# icE1usb-proto.net
KiCad netlist of a schematic drawn in EAGLE
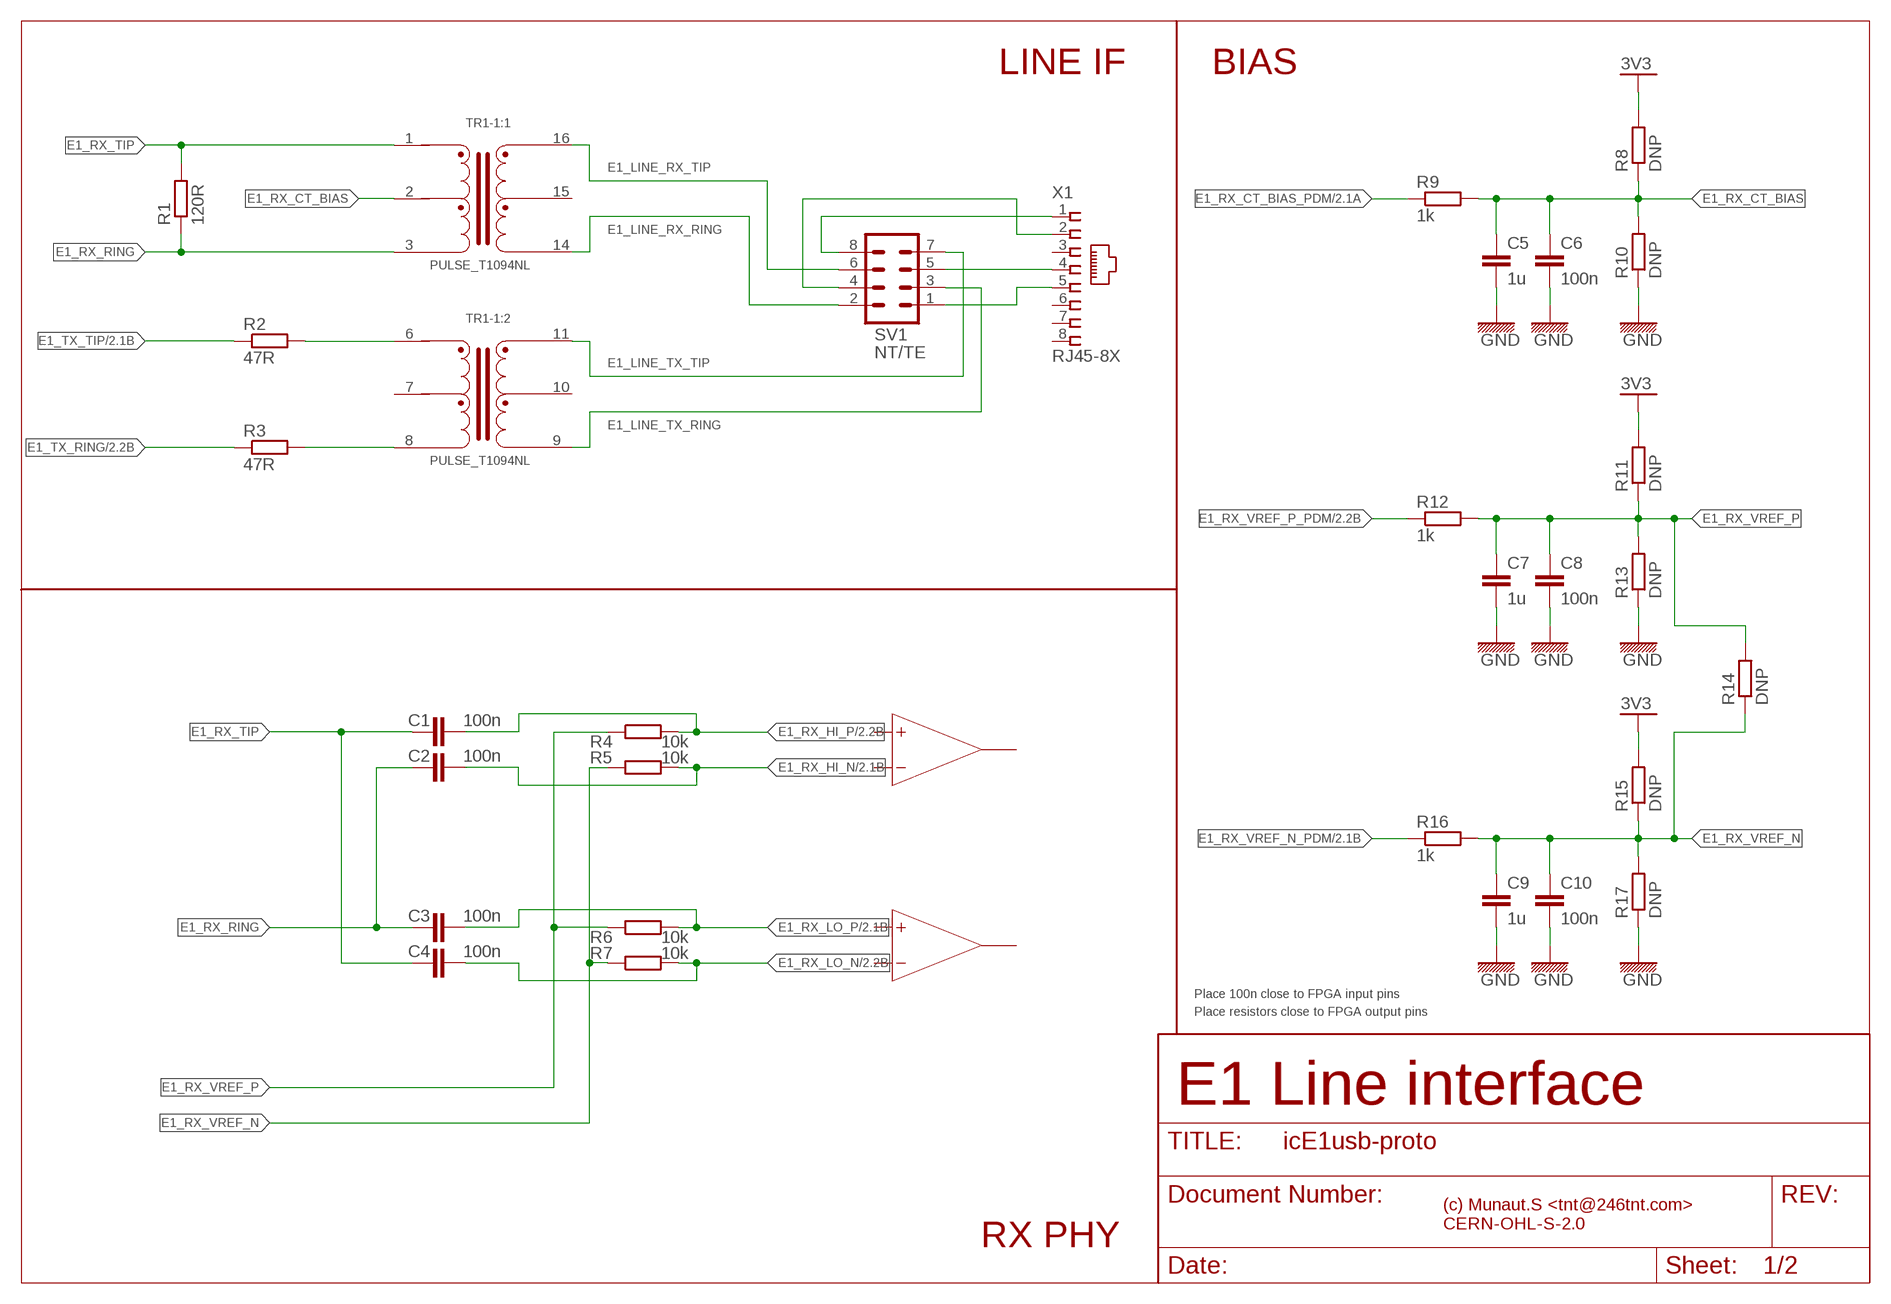
[diagram p0: schematic, sheet 1]
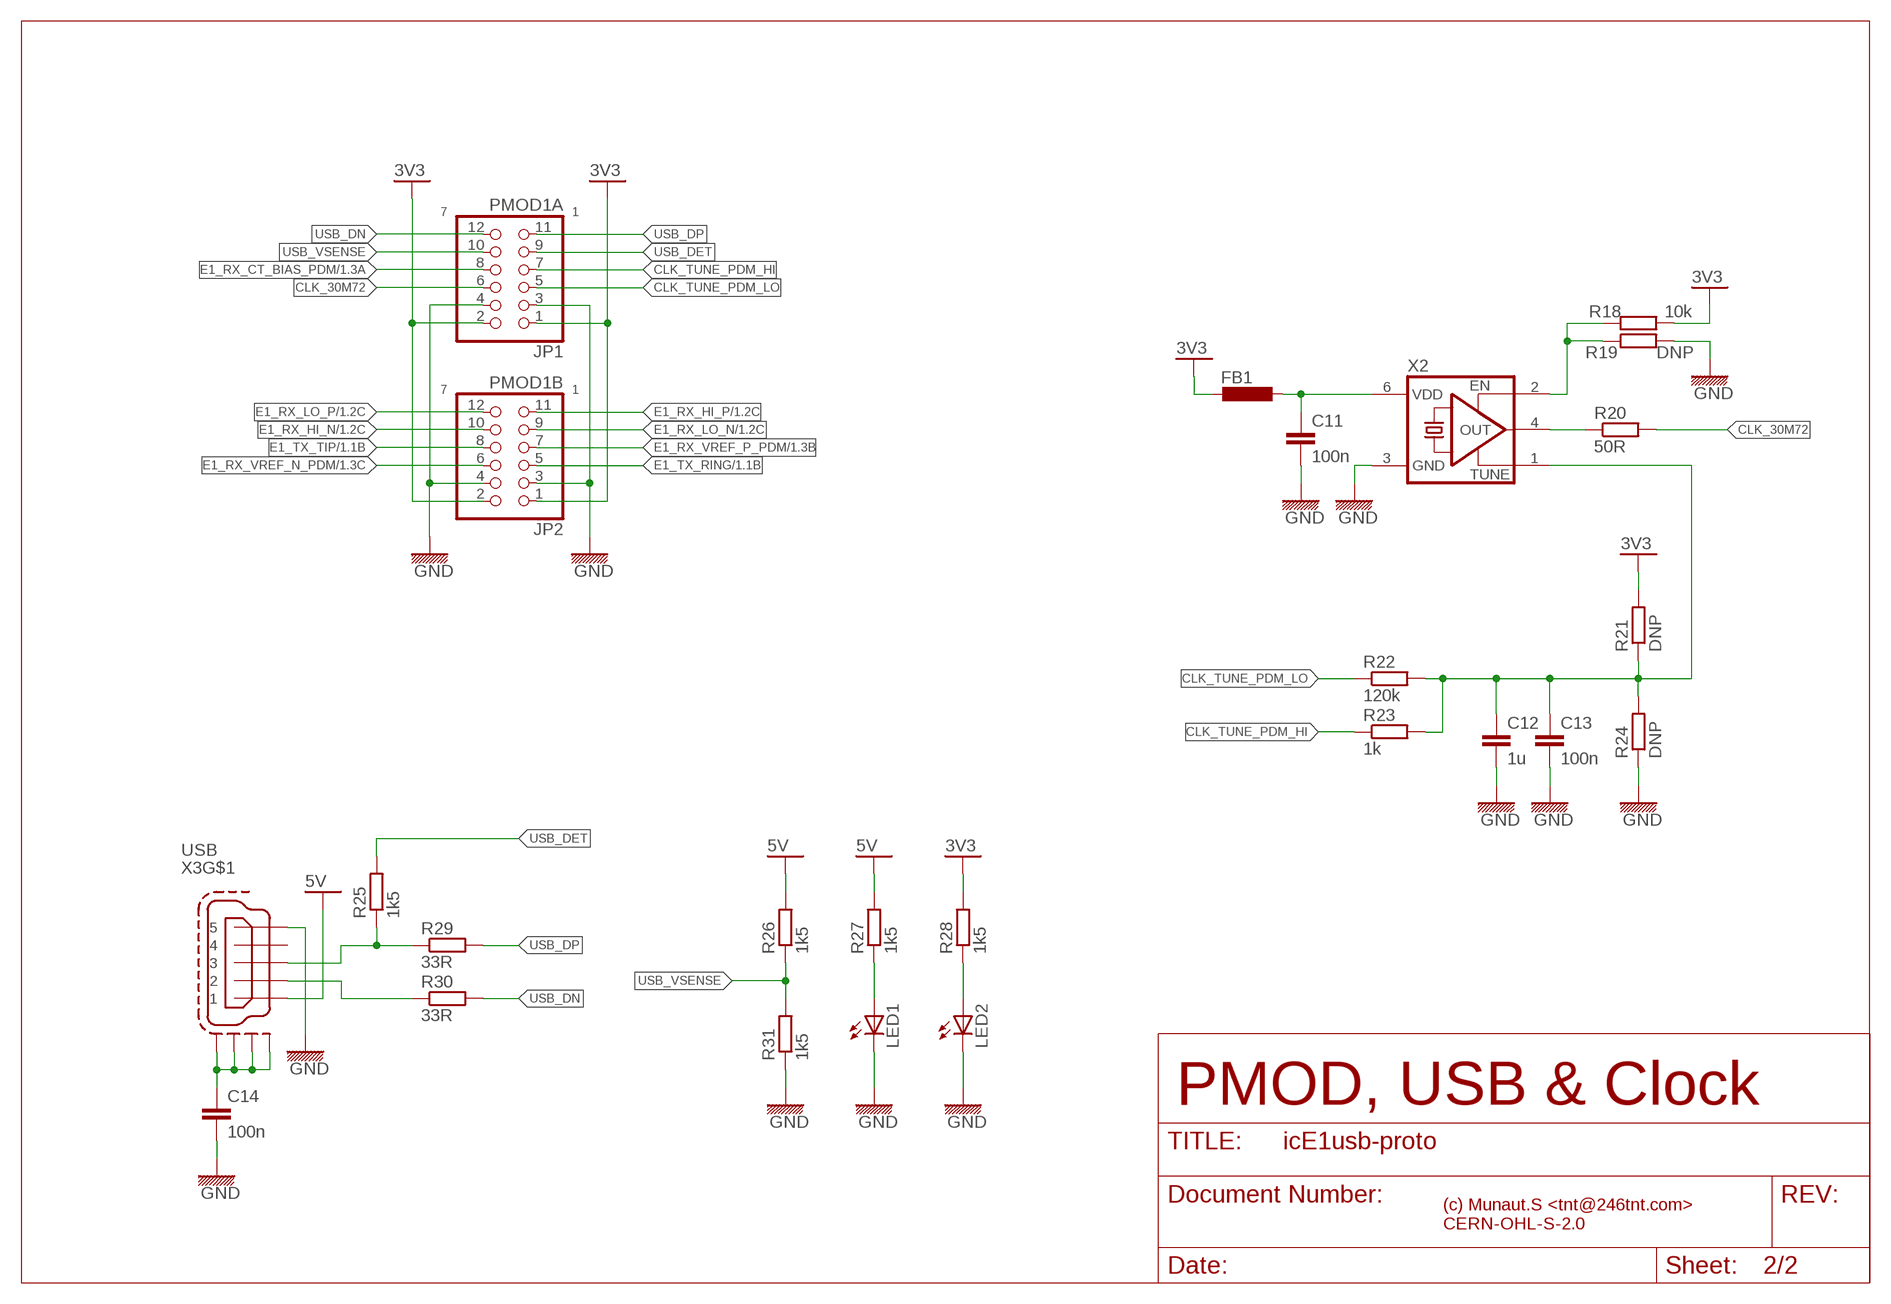
[diagram p1: schematic, sheet 2]

(export (version "E")
  (design (tool "Eeschema 10.0.6"))
  (components
    (comp (ref "C1")
      (value "100n")
      (footprint "eagle-import:0603")
      (libsource (lib "eagle-import") (part "C-EU_0603"))
    )
    (comp (ref "C2")
      (value "100n")
      (footprint "eagle-import:0603")
      (libsource (lib "eagle-import") (part "C-EU_0603"))
    )
    (comp (ref "C3")
      (value "100n")
      (footprint "eagle-import:0603")
      (libsource (lib "eagle-import") (part "C-EU_0603"))
    )
    (comp (ref "C4")
      (value "100n")
      (footprint "eagle-import:0603")
      (libsource (lib "eagle-import") (part "C-EU_0603"))
    )
    (comp (ref "C5")
      (value "1u")
      (footprint "eagle-import:0603")
      (libsource (lib "eagle-import") (part "C-EU_0603"))
    )
    (comp (ref "C6")
      (value "100n")
      (footprint "eagle-import:0603")
      (libsource (lib "eagle-import") (part "C-EU_0603"))
    )
    (comp (ref "C7")
      (value "1u")
      (footprint "eagle-import:0603")
      (libsource (lib "eagle-import") (part "C-EU_0603"))
    )
    (comp (ref "C8")
      (value "100n")
      (footprint "eagle-import:0603")
      (libsource (lib "eagle-import") (part "C-EU_0603"))
    )
    (comp (ref "C9")
      (value "1u")
      (footprint "eagle-import:0603")
      (libsource (lib "eagle-import") (part "C-EU_0603"))
    )
    (comp (ref "C10")
      (value "100n")
      (footprint "eagle-import:0603")
      (libsource (lib "eagle-import") (part "C-EU_0603"))
    )
    (comp (ref "R1")
      (value "120R")
      (footprint "eagle-import:0603_A")
      (libsource (lib "eagle-import") (part "R-EU_0603_A"))
    )
    (comp (ref "R2")
      (value "47R")
      (footprint "eagle-import:0603_A")
      (libsource (lib "eagle-import") (part "R-EU_0603_A"))
    )
    (comp (ref "R3")
      (value "47R")
      (footprint "eagle-import:0603_A")
      (libsource (lib "eagle-import") (part "R-EU_0603_A"))
    )
    (comp (ref "R4")
      (value "10k")
      (footprint "eagle-import:0603_A")
      (libsource (lib "eagle-import") (part "R-EU_0603_A"))
    )
    (comp (ref "R5")
      (value "10k")
      (footprint "eagle-import:0603_A")
      (libsource (lib "eagle-import") (part "R-EU_0603_A"))
    )
    (comp (ref "R6")
      (value "10k")
      (footprint "eagle-import:0603_A")
      (libsource (lib "eagle-import") (part "R-EU_0603_A"))
    )
    (comp (ref "R7")
      (value "10k")
      (footprint "eagle-import:0603_A")
      (libsource (lib "eagle-import") (part "R-EU_0603_A"))
    )
    (comp (ref "R8")
      (value "DNP")
      (footprint "eagle-import:0603_A")
      (libsource (lib "eagle-import") (part "R-EU_0603_A"))
    )
    (comp (ref "R9")
      (value "1k")
      (footprint "eagle-import:0603_A")
      (libsource (lib "eagle-import") (part "R-EU_0603_A"))
    )
    (comp (ref "R10")
      (value "DNP")
      (footprint "eagle-import:0603_A")
      (libsource (lib "eagle-import") (part "R-EU_0603_A"))
    )
    (comp (ref "R11")
      (value "DNP")
      (footprint "eagle-import:0603_A")
      (libsource (lib "eagle-import") (part "R-EU_0603_A"))
    )
    (comp (ref "R12")
      (value "1k")
      (footprint "eagle-import:0603_A")
      (libsource (lib "eagle-import") (part "R-EU_0603_A"))
    )
    (comp (ref "R13")
      (value "DNP")
      (footprint "eagle-import:0603_A")
      (libsource (lib "eagle-import") (part "R-EU_0603_A"))
    )
    (comp (ref "R14")
      (value "DNP")
      (footprint "eagle-import:0603_A")
      (libsource (lib "eagle-import") (part "R-EU_0603_A"))
    )
    (comp (ref "R15")
      (value "DNP")
      (footprint "eagle-import:0603_A")
      (libsource (lib "eagle-import") (part "R-EU_0603_A"))
    )
    (comp (ref "R16")
      (value "1k")
      (footprint "eagle-import:0603_A")
      (libsource (lib "eagle-import") (part "R-EU_0603_A"))
    )
    (comp (ref "R17")
      (value "DNP")
      (footprint "eagle-import:0603_A")
      (libsource (lib "eagle-import") (part "R-EU_0603_A"))
    )
    (comp (ref "SV1")
      (value "NT/TE")
      (footprint "eagle-import:MA04-2")
      (libsource (lib "eagle-import") (part "MA04-2"))
    )
    (comp (ref "TR1")
      (value "PULSE_T1094NL")
      (footprint "eagle-import:PULSE_BH")
      (libsource (lib "eagle-import") (part "PULSE_T1094NL"))
    )
    (comp (ref "X1")
      (value "RJ45-8X")
      (footprint "eagle-import:RJ45-NO-SHIELD")
      (libsource (lib "eagle-import") (part "RJ45-8X"))
    )
    (comp (ref "C11")
      (value "100n")
      (footprint "eagle-import:0603")
      (libsource (lib "eagle-import") (part "C-EU_0603"))
    )
    (comp (ref "C12")
      (value "1u")
      (footprint "eagle-import:0603")
      (libsource (lib "eagle-import") (part "C-EU_0603"))
    )
    (comp (ref "C13")
      (value "100n")
      (footprint "eagle-import:0603")
      (libsource (lib "eagle-import") (part "C-EU_0603"))
    )
    (comp (ref "C14")
      (value "100n")
      (footprint "eagle-import:0603")
      (libsource (lib "eagle-import") (part "C-EU_0603"))
    )
    (comp (ref "FB1")
      (value "FBEAD_0603")
      (footprint "eagle-import:0603")
      (libsource (lib "eagle-import") (part "FBEAD_0603"))
    )
    (comp (ref "JP1")
      (value "PMOD1A")
      (footprint "eagle-import:2X06_90")
      (libsource (lib "eagle-import") (part "PINHD-2X6/90"))
    )
    (comp (ref "JP2")
      (value "PMOD1B")
      (footprint "eagle-import:2X06_90")
      (libsource (lib "eagle-import") (part "PINHD-2X6/90"))
    )
    (comp (ref "LED1")
      (value "LEDCHIPLED_0603")
      (footprint "eagle-import:CHIPLED_0603")
      (libsource (lib "eagle-import") (part "LEDCHIPLED_0603"))
    )
    (comp (ref "LED2")
      (value "LEDCHIPLED_0603")
      (footprint "eagle-import:CHIPLED_0603")
      (libsource (lib "eagle-import") (part "LEDCHIPLED_0603"))
    )
    (comp (ref "R18")
      (value "10k")
      (footprint "eagle-import:0603_A")
      (libsource (lib "eagle-import") (part "R-EU_0603_A"))
    )
    (comp (ref "R19")
      (value "DNP")
      (footprint "eagle-import:0603_A")
      (libsource (lib "eagle-import") (part "R-EU_0603_A"))
    )
    (comp (ref "R20")
      (value "50R")
      (footprint "eagle-import:0603_A")
      (libsource (lib "eagle-import") (part "R-EU_0603_A"))
    )
    (comp (ref "R21")
      (value "DNP")
      (footprint "eagle-import:0603_A")
      (libsource (lib "eagle-import") (part "R-EU_0603_A"))
    )
    (comp (ref "R22")
      (value "120k")
      (footprint "eagle-import:0603_A")
      (libsource (lib "eagle-import") (part "R-EU_0603_A"))
    )
    (comp (ref "R23")
      (value "1k")
      (footprint "eagle-import:0603_A")
      (libsource (lib "eagle-import") (part "R-EU_0603_A"))
    )
    (comp (ref "R24")
      (value "DNP")
      (footprint "eagle-import:0603_A")
      (libsource (lib "eagle-import") (part "R-EU_0603_A"))
    )
    (comp (ref "R25")
      (value "1k5")
      (footprint "eagle-import:0603_A")
      (libsource (lib "eagle-import") (part "R-EU_0603_A"))
    )
    (comp (ref "R26")
      (value "1k5")
      (footprint "eagle-import:0603_A")
      (libsource (lib "eagle-import") (part "R-EU_0603_A"))
    )
    (comp (ref "R27")
      (value "1k5")
      (footprint "eagle-import:0603_A")
      (libsource (lib "eagle-import") (part "R-EU_0603_A"))
    )
    (comp (ref "R28")
      (value "1k5")
      (footprint "eagle-import:0603_A")
      (libsource (lib "eagle-import") (part "R-EU_0603_A"))
    )
    (comp (ref "R29")
      (value "33R")
      (footprint "eagle-import:0603_A")
      (libsource (lib "eagle-import") (part "R-EU_0603_A"))
    )
    (comp (ref "R30")
      (value "33R")
      (footprint "eagle-import:0603_A")
      (libsource (lib "eagle-import") (part "R-EU_0603_A"))
    )
    (comp (ref "R31")
      (value "1k5")
      (footprint "eagle-import:0603_A")
      (libsource (lib "eagle-import") (part "R-EU_0603_A"))
    )
    (comp (ref "X2")
      (value "XTAL_OSC_ET_CFPV-45/46")
      (footprint "eagle-import:CFPV-45_46")
      (libsource (lib "eagle-import") (part "XTAL_OSC_ET_CFPV-45/46"))
    )
    (comp (ref "X3")
      (value "USB")
      (footprint "eagle-import:32005-201")
      (libsource (lib "eagle-import") (part "MINI-USB-SCHIELD-32005-201"))
    )
  )
  (nets
    (net (code "1") (name "3V3") (class "Default")
      (node (ref "FB1") (pin "1") (pinfunction "1_1") (pintype "passive"))
      (node (ref "JP1") (pin "1") (pinfunction "1_1") (pintype "passive"))
      (node (ref "JP1") (pin "2") (pinfunction "2_2") (pintype "passive"))
      (node (ref "JP2") (pin "1") (pinfunction "1_1") (pintype "passive"))
      (node (ref "JP2") (pin "2") (pinfunction "2_2") (pintype "passive"))
      (node (ref "R11") (pin "2") (pinfunction "2_2") (pintype "passive"))
      (node (ref "R15") (pin "2") (pinfunction "2_2") (pintype "passive"))
      (node (ref "R18") (pin "2") (pinfunction "2_2") (pintype "passive"))
      (node (ref "R21") (pin "2") (pinfunction "2_2") (pintype "passive"))
      (node (ref "R28") (pin "2") (pinfunction "2_2") (pintype "passive"))
      (node (ref "R8") (pin "2") (pinfunction "2_2") (pintype "passive"))
    )
    (net (code "2") (name "5V") (class "Default")
      (node (ref "R26") (pin "2") (pinfunction "2_2") (pintype "passive"))
      (node (ref "R27") (pin "2") (pinfunction "2_2") (pintype "passive"))
      (node (ref "X3") (pin "1") (pinfunction "1_1") (pintype "passive"))
    )
    (net (code "3") (name "CLK_30M72") (class "Default")
      (node (ref "JP1") (pin "6") (pinfunction "6_6") (pintype "passive"))
      (node (ref "R20") (pin "2") (pinfunction "2_2") (pintype "passive"))
    )
    (net (code "4") (name "CLK_TUNE_PDM_HI") (class "Default")
      (node (ref "JP1") (pin "7") (pinfunction "7_7") (pintype "passive"))
      (node (ref "R23") (pin "1") (pinfunction "1_1") (pintype "passive"))
    )
    (net (code "5") (name "CLK_TUNE_PDM_LO") (class "Default")
      (node (ref "JP1") (pin "5") (pinfunction "5_5") (pintype "passive"))
      (node (ref "R22") (pin "1") (pinfunction "1_1") (pintype "passive"))
    )
    (net (code "6") (name "E1_LINE_RX_RING") (class "Default")
      (node (ref "SV1") (pin "2") (pinfunction "2_2") (pintype "passive"))
      (node (ref "TR1") (pin "14") (pinfunction "P$3_14") (pintype "bidirectional"))
    )
    (net (code "7") (name "E1_LINE_RX_TIP") (class "Default")
      (node (ref "SV1") (pin "6") (pinfunction "6_6") (pintype "passive"))
      (node (ref "TR1") (pin "16") (pinfunction "P$1_16") (pintype "bidirectional"))
    )
    (net (code "8") (name "E1_LINE_TX_RING") (class "Default")
      (node (ref "SV1") (pin "3") (pinfunction "3_3") (pintype "passive"))
      (node (ref "TR1") (pin "9") (pinfunction "P$3_9") (pintype "bidirectional"))
    )
    (net (code "9") (name "E1_LINE_TX_TIP") (class "Default")
      (node (ref "SV1") (pin "7") (pinfunction "7_7") (pintype "passive"))
      (node (ref "TR1") (pin "11") (pinfunction "P$1_11") (pintype "bidirectional"))
    )
    (net (code "10") (name "E1_RX_CT_BIAS") (class "Default")
      (node (ref "C5") (pin "1") (pinfunction "1_1") (pintype "passive"))
      (node (ref "C6") (pin "1") (pinfunction "1_1") (pintype "passive"))
      (node (ref "R10") (pin "2") (pinfunction "2_2") (pintype "passive"))
      (node (ref "R8") (pin "1") (pinfunction "1_1") (pintype "passive"))
      (node (ref "R9") (pin "2") (pinfunction "2_2") (pintype "passive"))
      (node (ref "TR1") (pin "2") (pinfunction "P$5_2") (pintype "bidirectional"))
    )
    (net (code "11") (name "E1_RX_CT_BIAS_PDM") (class "Default")
      (node (ref "JP1") (pin "8") (pinfunction "8_8") (pintype "passive"))
      (node (ref "R9") (pin "1") (pinfunction "1_1") (pintype "passive"))
    )
    (net (code "12") (name "E1_RX_HI_N") (class "Default")
      (node (ref "C2") (pin "2") (pinfunction "2_2") (pintype "passive"))
      (node (ref "JP2") (pin "10") (pinfunction "10_10") (pintype "passive"))
      (node (ref "R5") (pin "2") (pinfunction "2_2") (pintype "passive"))
    )
    (net (code "13") (name "E1_RX_HI_P") (class "Default")
      (node (ref "C1") (pin "2") (pinfunction "2_2") (pintype "passive"))
      (node (ref "JP2") (pin "11") (pinfunction "11_11") (pintype "passive"))
      (node (ref "R4") (pin "2") (pinfunction "2_2") (pintype "passive"))
    )
    (net (code "14") (name "E1_RX_LO_N") (class "Default")
      (node (ref "C4") (pin "2") (pinfunction "2_2") (pintype "passive"))
      (node (ref "JP2") (pin "9") (pinfunction "9_9") (pintype "passive"))
      (node (ref "R7") (pin "2") (pinfunction "2_2") (pintype "passive"))
    )
    (net (code "15") (name "E1_RX_LO_P") (class "Default")
      (node (ref "C3") (pin "2") (pinfunction "2_2") (pintype "passive"))
      (node (ref "JP2") (pin "12") (pinfunction "12_12") (pintype "passive"))
      (node (ref "R6") (pin "2") (pinfunction "2_2") (pintype "passive"))
    )
    (net (code "16") (name "E1_RX_RING") (class "Default")
      (node (ref "C2") (pin "1") (pinfunction "1_1") (pintype "passive"))
      (node (ref "C3") (pin "1") (pinfunction "1_1") (pintype "passive"))
      (node (ref "R1") (pin "1") (pinfunction "1_1") (pintype "passive"))
      (node (ref "TR1") (pin "3") (pinfunction "P$6_3") (pintype "bidirectional"))
    )
    (net (code "17") (name "E1_RX_TIP") (class "Default")
      (node (ref "C1") (pin "1") (pinfunction "1_1") (pintype "passive"))
      (node (ref "C4") (pin "1") (pinfunction "1_1") (pintype "passive"))
      (node (ref "R1") (pin "2") (pinfunction "2_2") (pintype "passive"))
      (node (ref "TR1") (pin "1") (pinfunction "P$4_1") (pintype "bidirectional"))
    )
    (net (code "18") (name "E1_RX_VREF_N") (class "Default")
      (node (ref "C10") (pin "1") (pinfunction "1_1") (pintype "passive"))
      (node (ref "C9") (pin "1") (pinfunction "1_1") (pintype "passive"))
      (node (ref "R14") (pin "1") (pinfunction "1_1") (pintype "passive"))
      (node (ref "R15") (pin "1") (pinfunction "1_1") (pintype "passive"))
      (node (ref "R16") (pin "2") (pinfunction "2_2") (pintype "passive"))
      (node (ref "R17") (pin "2") (pinfunction "2_2") (pintype "passive"))
      (node (ref "R5") (pin "1") (pinfunction "1_1") (pintype "passive"))
      (node (ref "R7") (pin "1") (pinfunction "1_1") (pintype "passive"))
    )
    (net (code "19") (name "E1_RX_VREF_N_PDM") (class "Default")
      (node (ref "JP2") (pin "6") (pinfunction "6_6") (pintype "passive"))
      (node (ref "R16") (pin "1") (pinfunction "1_1") (pintype "passive"))
    )
    (net (code "20") (name "E1_RX_VREF_P") (class "Default")
      (node (ref "C7") (pin "1") (pinfunction "1_1") (pintype "passive"))
      (node (ref "C8") (pin "1") (pinfunction "1_1") (pintype "passive"))
      (node (ref "R11") (pin "1") (pinfunction "1_1") (pintype "passive"))
      (node (ref "R12") (pin "2") (pinfunction "2_2") (pintype "passive"))
      (node (ref "R13") (pin "2") (pinfunction "2_2") (pintype "passive"))
      (node (ref "R14") (pin "2") (pinfunction "2_2") (pintype "passive"))
      (node (ref "R4") (pin "1") (pinfunction "1_1") (pintype "passive"))
      (node (ref "R6") (pin "1") (pinfunction "1_1") (pintype "passive"))
    )
    (net (code "21") (name "E1_RX_VREF_P_PDM") (class "Default")
      (node (ref "JP2") (pin "7") (pinfunction "7_7") (pintype "passive"))
      (node (ref "R12") (pin "1") (pinfunction "1_1") (pintype "passive"))
    )
    (net (code "22") (name "E1_TX_RING") (class "Default")
      (node (ref "JP2") (pin "5") (pinfunction "5_5") (pintype "passive"))
      (node (ref "R3") (pin "1") (pinfunction "1_1") (pintype "passive"))
    )
    (net (code "23") (name "E1_TX_TIP") (class "Default")
      (node (ref "JP2") (pin "8") (pinfunction "8_8") (pintype "passive"))
      (node (ref "R2") (pin "1") (pinfunction "1_1") (pintype "passive"))
    )
    (net (code "24") (name "GND") (class "Default")
      (node (ref "C10") (pin "2") (pinfunction "2_2") (pintype "passive"))
      (node (ref "C11") (pin "2") (pinfunction "2_2") (pintype "passive"))
      (node (ref "C12") (pin "2") (pinfunction "2_2") (pintype "passive"))
      (node (ref "C13") (pin "2") (pinfunction "2_2") (pintype "passive"))
      (node (ref "C14") (pin "2") (pinfunction "2_2") (pintype "passive"))
      (node (ref "C5") (pin "2") (pinfunction "2_2") (pintype "passive"))
      (node (ref "C6") (pin "2") (pinfunction "2_2") (pintype "passive"))
      (node (ref "C7") (pin "2") (pinfunction "2_2") (pintype "passive"))
      (node (ref "C8") (pin "2") (pinfunction "2_2") (pintype "passive"))
      (node (ref "C9") (pin "2") (pinfunction "2_2") (pintype "passive"))
      (node (ref "JP1") (pin "3") (pinfunction "3_3") (pintype "passive"))
      (node (ref "JP1") (pin "4") (pinfunction "4_4") (pintype "passive"))
      (node (ref "JP2") (pin "3") (pinfunction "3_3") (pintype "passive"))
      (node (ref "JP2") (pin "4") (pinfunction "4_4") (pintype "passive"))
      (node (ref "LED1") (pin "C") (pinfunction "C_C") (pintype "passive"))
      (node (ref "LED2") (pin "C") (pinfunction "C_C") (pintype "passive"))
      (node (ref "R10") (pin "1") (pinfunction "1_1") (pintype "passive"))
      (node (ref "R13") (pin "1") (pinfunction "1_1") (pintype "passive"))
      (node (ref "R17") (pin "1") (pinfunction "1_1") (pintype "passive"))
      (node (ref "R19") (pin "2") (pinfunction "2_2") (pintype "passive"))
      (node (ref "R24") (pin "1") (pinfunction "1_1") (pintype "passive"))
      (node (ref "R31") (pin "1") (pinfunction "1_1") (pintype "passive"))
      (node (ref "X2") (pin "3") (pinfunction "GND_3") (pintype "power_in"))
      (node (ref "X3") (pin "5") (pinfunction "5_5") (pintype "passive"))
    )
    (net (code "25") (name "Net-(LED1-PadA)") (class "Default")
      (node (ref "LED1") (pin "A") (pinfunction "A_A") (pintype "passive"))
      (node (ref "R27") (pin "1") (pinfunction "1_1") (pintype "passive"))
    )
    (net (code "26") (name "Net-(LED2-PadA)") (class "Default")
      (node (ref "LED2") (pin "A") (pinfunction "A_A") (pintype "passive"))
      (node (ref "R28") (pin "1") (pinfunction "1_1") (pintype "passive"))
    )
    (net (code "27") (name "Net-(R25-Pad1)") (class "Default")
      (node (ref "R25") (pin "1") (pinfunction "1_1") (pintype "passive"))
      (node (ref "R29") (pin "1") (pinfunction "1_1") (pintype "passive"))
      (node (ref "X3") (pin "3") (pinfunction "3_3") (pintype "passive"))
    )
    (net (code "28") (name "Net-(R30-Pad1)") (class "Default")
      (node (ref "R30") (pin "1") (pinfunction "1_1") (pintype "passive"))
      (node (ref "X3") (pin "2") (pinfunction "2_2") (pintype "passive"))
    )
    (net (code "29") (name "Net-(SV1-Pad1)") (class "Default")
      (node (ref "SV1") (pin "1") (pinfunction "1_1") (pintype "passive"))
      (node (ref "X1") (pin "5") (pinfunction "5_5") (pintype "passive"))
    )
    (net (code "30") (name "Net-(SV1-Pad4)") (class "Default")
      (node (ref "SV1") (pin "4") (pinfunction "4_4") (pintype "passive"))
      (node (ref "X1") (pin "2") (pinfunction "2_2") (pintype "passive"))
    )
    (net (code "31") (name "Net-(SV1-Pad5)") (class "Default")
      (node (ref "SV1") (pin "5") (pinfunction "5_5") (pintype "passive"))
      (node (ref "X1") (pin "4") (pinfunction "4_4") (pintype "passive"))
    )
    (net (code "32") (name "Net-(SV1-Pad8)") (class "Default")
      (node (ref "SV1") (pin "8") (pinfunction "8_8") (pintype "passive"))
      (node (ref "X1") (pin "1") (pinfunction "1_1") (pintype "passive"))
    )
    (net (code "33") (name "Net-(TR1B-P$4)") (class "Default")
      (node (ref "R2") (pin "2") (pinfunction "2_2") (pintype "passive"))
      (node (ref "TR1") (pin "6") (pinfunction "P$4_6") (pintype "bidirectional"))
    )
    (net (code "34") (name "Net-(TR1B-P$6)") (class "Default")
      (node (ref "R3") (pin "2") (pinfunction "2_2") (pintype "passive"))
      (node (ref "TR1") (pin "8") (pinfunction "P$6_8") (pintype "bidirectional"))
    )
    (net (code "35") (name "Net-(X2-EN)") (class "Default")
      (node (ref "R18") (pin "1") (pinfunction "1_1") (pintype "passive"))
      (node (ref "R19") (pin "1") (pinfunction "1_1") (pintype "passive"))
      (node (ref "X2") (pin "2") (pinfunction "EN_2") (pintype "input"))
    )
    (net (code "36") (name "Net-(X2-OUT)") (class "Default")
      (node (ref "R20") (pin "1") (pinfunction "1_1") (pintype "passive"))
      (node (ref "X2") (pin "4") (pinfunction "OUT_4") (pintype "output"))
    )
    (net (code "37") (name "Net-(X2-TUNE)") (class "Default")
      (node (ref "C12") (pin "1") (pinfunction "1_1") (pintype "passive"))
      (node (ref "C13") (pin "1") (pinfunction "1_1") (pintype "passive"))
      (node (ref "R21") (pin "1") (pinfunction "1_1") (pintype "passive"))
      (node (ref "R22") (pin "2") (pinfunction "2_2") (pintype "passive"))
      (node (ref "R23") (pin "2") (pinfunction "2_2") (pintype "passive"))
      (node (ref "R24") (pin "2") (pinfunction "2_2") (pintype "passive"))
      (node (ref "X2") (pin "1") (pinfunction "TUNE_1") (pintype "input"))
    )
    (net (code "38") (name "Net-(X2-VDD)") (class "Default")
      (node (ref "C11") (pin "1") (pinfunction "1_1") (pintype "passive"))
      (node (ref "FB1") (pin "2") (pinfunction "2_2") (pintype "passive"))
      (node (ref "X2") (pin "6") (pinfunction "VDD_6") (pintype "power_in"))
    )
    (net (code "39") (name "Net-(X3B-S1)") (class "Default")
      (node (ref "C14") (pin "1") (pinfunction "1_1") (pintype "passive"))
      (node (ref "X3") (pin "M1") (pinfunction "S1_M1") (pintype "passive"))
      (node (ref "X3") (pin "M2") (pinfunction "S2_M2") (pintype "passive"))
      (node (ref "X3") (pin "M3") (pinfunction "S3_M3") (pintype "passive"))
      (node (ref "X3") (pin "M4") (pinfunction "S4_M4") (pintype "passive"))
    )
    (net (code "40") (name "USB_DET") (class "Default")
      (node (ref "JP1") (pin "9") (pinfunction "9_9") (pintype "passive"))
      (node (ref "R25") (pin "2") (pinfunction "2_2") (pintype "passive"))
    )
    (net (code "41") (name "USB_DN") (class "Default")
      (node (ref "JP1") (pin "12") (pinfunction "12_12") (pintype "passive"))
      (node (ref "R30") (pin "2") (pinfunction "2_2") (pintype "passive"))
    )
    (net (code "42") (name "USB_DP") (class "Default")
      (node (ref "JP1") (pin "11") (pinfunction "11_11") (pintype "passive"))
      (node (ref "R29") (pin "2") (pinfunction "2_2") (pintype "passive"))
    )
    (net (code "43") (name "USB_VSENSE") (class "Default")
      (node (ref "JP1") (pin "10") (pinfunction "10_10") (pintype "passive"))
      (node (ref "R26") (pin "1") (pinfunction "1_1") (pintype "passive"))
      (node (ref "R31") (pin "2") (pinfunction "2_2") (pintype "passive"))
    )
    (net (code "44") (name "unconnected-(TR1A-P$2-Pad15)") (class "Default")
      (node (ref "TR1") (pin "15") (pinfunction "P$2_15") (pintype "bidirectional"))
    )
    (net (code "45") (name "unconnected-(TR1B-P$2-Pad10)") (class "Default")
      (node (ref "TR1") (pin "10") (pinfunction "P$2_10") (pintype "bidirectional"))
    )
    (net (code "46") (name "unconnected-(TR1B-P$5-Pad7)") (class "Default")
      (node (ref "TR1") (pin "7") (pinfunction "P$5_7") (pintype "bidirectional"))
    )
    (net (code "47") (name "unconnected-(X1-Pad3)") (class "Default")
      (node (ref "X1") (pin "3") (pinfunction "3_3") (pintype "passive"))
    )
    (net (code "48") (name "unconnected-(X1-Pad6)") (class "Default")
      (node (ref "X1") (pin "6") (pinfunction "6_6") (pintype "passive"))
    )
    (net (code "49") (name "unconnected-(X1-Pad7)") (class "Default")
      (node (ref "X1") (pin "7") (pinfunction "7_7") (pintype "passive"))
    )
    (net (code "50") (name "unconnected-(X1-Pad8)") (class "Default")
      (node (ref "X1") (pin "8") (pinfunction "8_8") (pintype "passive"))
    )
    (net (code "51") (name "unconnected-(X3-Pad4)") (class "Default")
      (node (ref "X3") (pin "4") (pinfunction "4_4") (pintype "passive"))
    )
  )
)
